# main.net
KiCad netlist of a schematic drawn in EAGLE
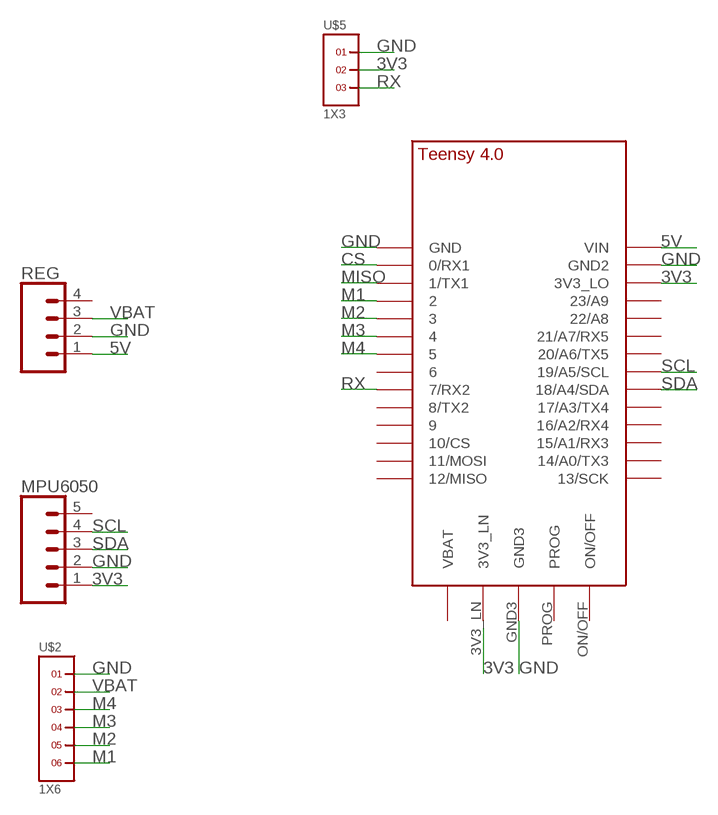
[diagram p0: schematic, sheet 1]

(export (version "E")
  (design (tool "Eeschema 10.0.6"))
  (components
    (comp (ref "MPU6050")
      (value "CONN_05NO_SILK")
      (footprint "eagle-import:1X05_NO_SILK")
      (libsource (lib "eagle-import") (part "CONN_05NO_SILK"))
    )
    (comp (ref "REG")
      (value "CONN_041X04_NO_SILK")
      (footprint "eagle-import:1X04_NO_SILK")
      (libsource (lib "eagle-import") (part "CONN_041X04_NO_SILK"))
    )
    (comp (ref "U$1")
      (value "TEENSY_4.0")
      (footprint "eagle-import:TEENSY_4.0")
      (libsource (lib "eagle-import") (part "TEENSY_4.0"))
    )
    (comp (ref "U$2")
      (value "1X6")
      (footprint "eagle-import:1X6")
      (libsource (lib "eagle-import") (part "1X6"))
    )
    (comp (ref "U$5")
      (value "1X3")
      (footprint "eagle-import:1X3")
      (libsource (lib "eagle-import") (part "1X3"))
    )
  )
  (nets
    (net (code "1") (name "/3V3") (class "Default")
      (node (ref "MPU6050") (pin "1") (pinfunction "1_1") (pintype "passive"))
      (node (ref "U$1") (pin "3V3_LN") (pinfunction "3V3_LN_3V3_LN") (pintype "bidirectional"))
      (node (ref "U$1") (pin "3V3_LO") (pinfunction "3V3_LO_3V3_LO") (pintype "bidirectional"))
      (node (ref "U$5") (pin "2") (pinfunction "2_2") (pintype "bidirectional"))
    )
    (net (code "2") (name "/5V") (class "Default")
      (node (ref "REG") (pin "1") (pinfunction "1_1") (pintype "passive"))
      (node (ref "U$1") (pin "VIN") (pinfunction "VIN_VIN") (pintype "bidirectional"))
    )
    (net (code "3") (name "/CS") (class "Default")
      (node (ref "U$1") (pin "0/RX") (pinfunction "0/RX1_0/RX") (pintype "bidirectional"))
    )
    (net (code "4") (name "/GND") (class "Default")
      (node (ref "MPU6050") (pin "2") (pinfunction "2_2") (pintype "passive"))
      (node (ref "REG") (pin "2") (pinfunction "2_2") (pintype "passive"))
      (node (ref "U$1") (pin "GND") (pinfunction "GND_GND") (pintype "bidirectional"))
      (node (ref "U$1") (pin "GND2") (pinfunction "GND2_GND2") (pintype "bidirectional"))
      (node (ref "U$1") (pin "GND3") (pinfunction "GND3_GND3") (pintype "bidirectional"))
      (node (ref "U$2") (pin "1") (pinfunction "1_1") (pintype "bidirectional"))
      (node (ref "U$5") (pin "1") (pinfunction "1_1") (pintype "bidirectional"))
    )
    (net (code "5") (name "/M1") (class "Default")
      (node (ref "U$1") (pin "2") (pinfunction "2_2") (pintype "bidirectional"))
      (node (ref "U$2") (pin "6") (pinfunction "6_6") (pintype "bidirectional"))
    )
    (net (code "6") (name "/M2") (class "Default")
      (node (ref "U$1") (pin "3/CANTX") (pinfunction "3_3/CANTX") (pintype "bidirectional"))
      (node (ref "U$2") (pin "5") (pinfunction "5_5") (pintype "bidirectional"))
    )
    (net (code "7") (name "/M3") (class "Default")
      (node (ref "U$1") (pin "4/CANRX") (pinfunction "4_4/CANRX") (pintype "bidirectional"))
      (node (ref "U$2") (pin "4") (pinfunction "4_4") (pintype "bidirectional"))
    )
    (net (code "8") (name "/M4") (class "Default")
      (node (ref "U$1") (pin "5") (pinfunction "5_5") (pintype "bidirectional"))
      (node (ref "U$2") (pin "3") (pinfunction "3_3") (pintype "bidirectional"))
    )
    (net (code "9") (name "/MISO") (class "Default")
      (node (ref "U$1") (pin "1/TX") (pinfunction "1/TX1_1/TX") (pintype "bidirectional"))
    )
    (net (code "10") (name "/RX") (class "Default")
      (node (ref "U$1") (pin "7") (pinfunction "7/RX2_7") (pintype "bidirectional"))
      (node (ref "U$5") (pin "3") (pinfunction "3_3") (pintype "bidirectional"))
    )
    (net (code "11") (name "/SCL") (class "Default")
      (node (ref "MPU6050") (pin "4") (pinfunction "4_4") (pintype "passive"))
      (node (ref "U$1") (pin "19/A5/SCL") (pinfunction "19/A5/SCL_19/A5/SCL") (pintype "bidirectional"))
    )
    (net (code "12") (name "/SDA") (class "Default")
      (node (ref "MPU6050") (pin "3") (pinfunction "3_3") (pintype "passive"))
      (node (ref "U$1") (pin "18/A4/SDA") (pinfunction "18/A4/SDA_18/A4/SDA") (pintype "bidirectional"))
    )
    (net (code "13") (name "/VBAT") (class "Default")
      (node (ref "REG") (pin "3") (pinfunction "3_3") (pintype "passive"))
      (node (ref "U$2") (pin "2") (pinfunction "2_2") (pintype "bidirectional"))
    )
    (net (code "14") (name "unconnected-(MPU6050-Pad5)") (class "Default")
      (node (ref "MPU6050") (pin "5") (pinfunction "5_5") (pintype "passive"))
    )
    (net (code "15") (name "unconnected-(REG-Pad4)") (class "Default")
      (node (ref "REG") (pin "4") (pinfunction "4_4") (pintype "passive"))
    )
    (net (code "16") (name "unconnected-(U$1-8{slash}TX2-Pad8)") (class "Default")
      (node (ref "U$1") (pin "8") (pinfunction "8/TX2_8") (pintype "bidirectional"))
    )
    (net (code "17") (name "unconnected-(U$1-9-Pad9{slash}CS)") (class "Default")
      (node (ref "U$1") (pin "9/CS") (pinfunction "9_9/CS") (pintype "bidirectional"))
    )
    (net (code "18") (name "unconnected-(U$1-14{slash}A0{slash}TX3-Pad14{slash}A0)") (class "Default")
      (node (ref "U$1") (pin "14/A0") (pinfunction "14/A0/TX3_14/A0") (pintype "bidirectional"))
    )
    (net (code "19") (name "unconnected-(U$1-15{slash}A1{slash}RX3-Pad15{slash}A1)") (class "Default")
      (node (ref "U$1") (pin "15/A1") (pinfunction "15/A1/RX3_15/A1") (pintype "bidirectional"))
    )
    (net (code "20") (name "unconnected-(U$1-16{slash}A2{slash}RX4-Pad16{slash}A2)") (class "Default")
      (node (ref "U$1") (pin "16/A2") (pinfunction "16/A2/RX4_16/A2") (pintype "bidirectional"))
    )
    (net (code "21") (name "unconnected-(U$1-17{slash}A3{slash}TX4-Pad17{slash}A3)") (class "Default")
      (node (ref "U$1") (pin "17/A3") (pinfunction "17/A3/TX4_17/A3") (pintype "bidirectional"))
    )
    (net (code "22") (name "unconnected-(U$1-20{slash}A6{slash}TX5-Pad20{slash}A6)") (class "Default")
      (node (ref "U$1") (pin "20/A6") (pinfunction "20/A6/TX5_20/A6") (pintype "bidirectional"))
    )
    (net (code "23") (name "unconnected-(U$1-21{slash}A7{slash}RX5-Pad21{slash}A7)") (class "Default")
      (node (ref "U$1") (pin "21/A7") (pinfunction "21/A7/RX5_21/A7") (pintype "bidirectional"))
    )
    (net (code "24") (name "unconnected-(U$1-Pad6)") (class "Default")
      (node (ref "U$1") (pin "6") (pinfunction "6_6") (pintype "bidirectional"))
    )
    (net (code "25") (name "unconnected-(U$1-Pad10{slash}CS)") (class "Default")
      (node (ref "U$1") (pin "10/CS") (pinfunction "10/CS_10/CS") (pintype "bidirectional"))
    )
    (net (code "26") (name "unconnected-(U$1-Pad11{slash}MOSI)") (class "Default")
      (node (ref "U$1") (pin "11/MOSI") (pinfunction "11/MOSI_11/MOSI") (pintype "bidirectional"))
    )
    (net (code "27") (name "unconnected-(U$1-Pad12{slash}MISO)") (class "Default")
      (node (ref "U$1") (pin "12/MISO") (pinfunction "12/MISO_12/MISO") (pintype "bidirectional"))
    )
    (net (code "28") (name "unconnected-(U$1-Pad13{slash}SCK)") (class "Default")
      (node (ref "U$1") (pin "13/SCK") (pinfunction "13/SCK_13/SCK") (pintype "bidirectional"))
    )
    (net (code "29") (name "unconnected-(U$1-Pad22{slash}A8)") (class "Default")
      (node (ref "U$1") (pin "22/A8") (pinfunction "22/A8_22/A8") (pintype "bidirectional"))
    )
    (net (code "30") (name "unconnected-(U$1-Pad23{slash}A9)") (class "Default")
      (node (ref "U$1") (pin "23/A9") (pinfunction "23/A9_23/A9") (pintype "bidirectional"))
    )
    (net (code "31") (name "unconnected-(U$1-PadON{slash}OFF)") (class "Default")
      (node (ref "U$1") (pin "ON/OFF") (pinfunction "ON/OFF_ON/OFF") (pintype "bidirectional"))
    )
    (net (code "32") (name "unconnected-(U$1-PadPROG)") (class "Default")
      (node (ref "U$1") (pin "PROG") (pinfunction "PROG_PROG") (pintype "bidirectional"))
    )
    (net (code "33") (name "unconnected-(U$1-VBAT-PadVBAT\\)") (class "Default")
      (node (ref "U$1") (pin "VBAT\\") (pinfunction "VBAT_VBAT\\") (pintype "bidirectional"))
    )
  )
)
